# PD_USB.net
KiCad netlist of a schematic drawn in Altium Designer
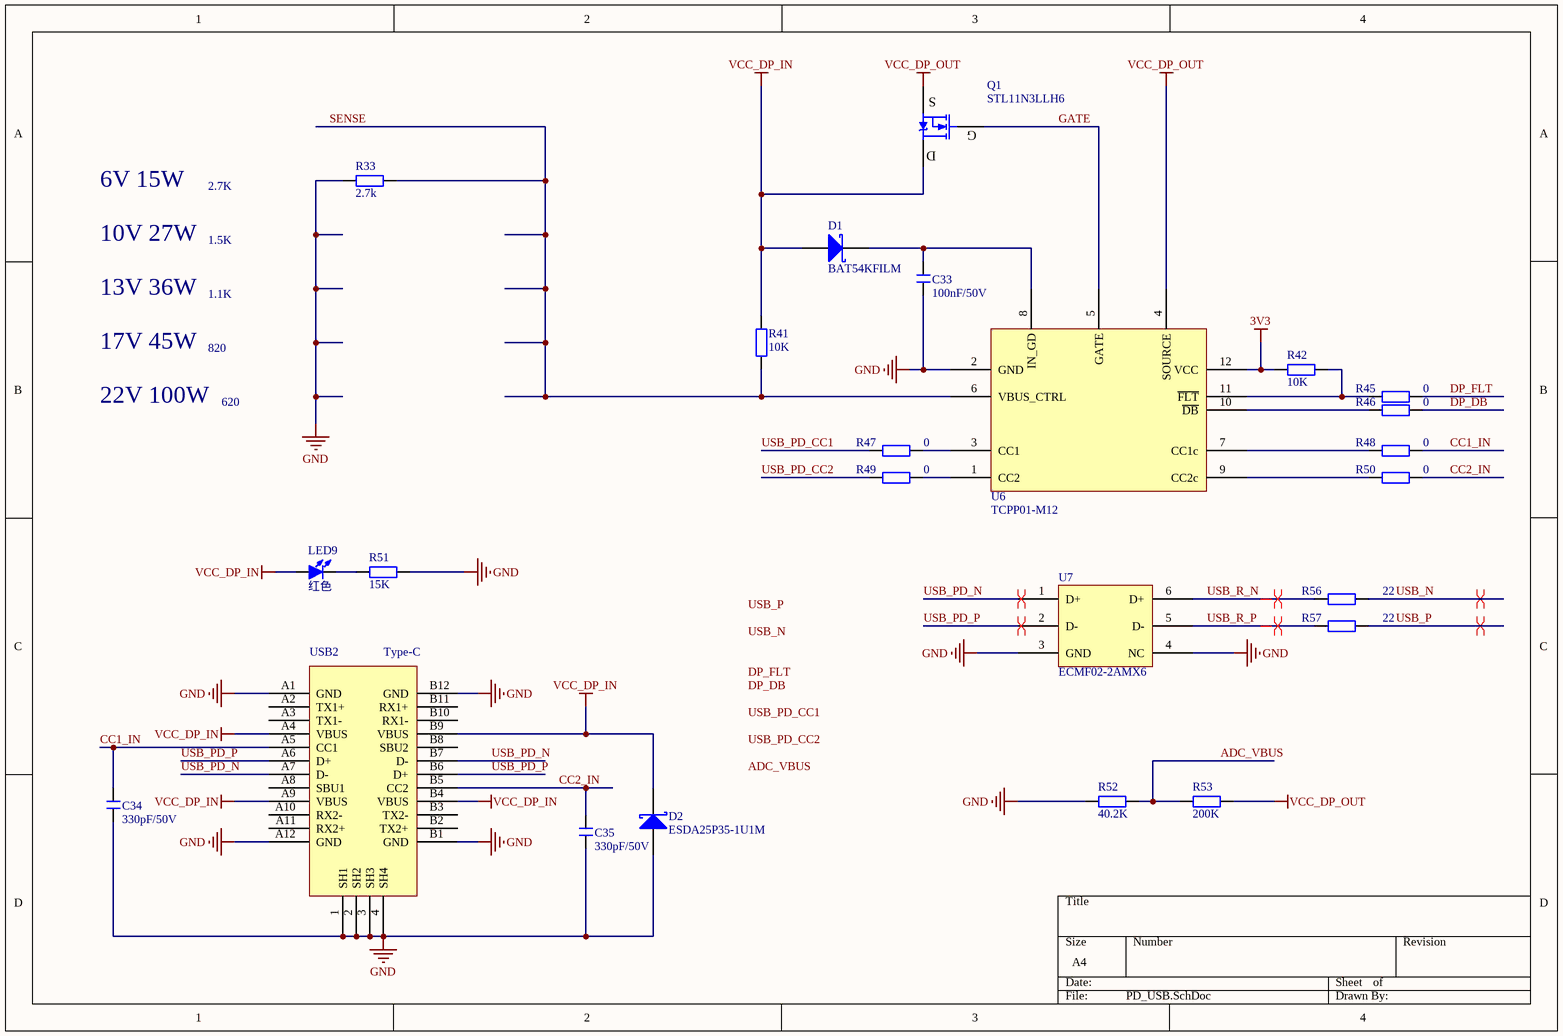
[diagram p0: PD_USB.SchDoc]

(export (version "E")
  (design (tool "Eeschema 10.0.6"))
  (components
    (comp (ref "C33")
      (value "100nF/50V")
      (footprint "C 0402_L")
      (description "贴片电容")
      (libsource (lib "3.1   - 电阻-电容-电感") (part "C"))
    )
    (comp (ref "C34")
      (value "330pF/50V")
      (footprint "C 0402_L")
      (description "贴片电容")
      (libsource (lib "3.1   - 电阻-电容-电感") (part "C"))
    )
    (comp (ref "C35")
      (value "330pF/50V")
      (footprint "C 0402_L")
      (description "贴片电容")
      (libsource (lib "3.1   - 电阻-电容-电感") (part "C"))
    )
    (comp (ref "D1")
      (value "BAT54KFILM")
      (footprint "BAT54KFILM")
      (description "Schottky Diode")
      (libsource (lib "Miscellaneous Devices") (part "D Schottky"))
    )
    (comp (ref "D2")
      (value "ESDA25P35-1U1M")
      (footprint "ESDA25P35-1U1M")
      (description "Schottky Diode")
      (libsource (lib "Miscellaneous Devices") (part "D Schottky"))
    )
    (comp (ref "LED9")
      (value "红色")
      (footprint "LED")
      (description "C84267")
      (libsource (lib "9.1   - LED") (part "LED-SMD"))
    )
    (comp (ref "Q1")
      (value "STL11N3LLH6")
      (footprint "STL11N3LLH6")
      (description "N沟道场效应管")
      (libsource (lib "6.1   - 场效应管-可控硅") (part "SI2302"))
    )
    (comp (ref "R33")
      (value "2.7k")
      (footprint "R 0402_L")
      (description "贴片电阻")
      (libsource (lib "3.1   - 电阻-电容-电感") (part "R"))
    )
    (comp (ref "R41")
      (value "10K")
      (footprint "R 0402_L")
      (description "贴片电阻")
      (libsource (lib "3.1   - 电阻-电容-电感") (part "R"))
    )
    (comp (ref "R42")
      (value "10K")
      (footprint "R 0402_L")
      (description "贴片电阻")
      (libsource (lib "3.1   - 电阻-电容-电感") (part "R"))
    )
    (comp (ref "R45")
      (value "0")
      (footprint "R 0402_L")
      (description "贴片电阻")
      (libsource (lib "3.1   - 电阻-电容-电感") (part "R"))
    )
    (comp (ref "R46")
      (value "0")
      (footprint "R 0402_L")
      (description "贴片电阻")
      (libsource (lib "3.1   - 电阻-电容-电感") (part "R"))
    )
    (comp (ref "R47")
      (value "0")
      (footprint "R 0402_L")
      (description "贴片电阻")
      (libsource (lib "3.1   - 电阻-电容-电感") (part "R"))
    )
    (comp (ref "R48")
      (value "0")
      (footprint "R 0402_L")
      (description "贴片电阻")
      (libsource (lib "3.1   - 电阻-电容-电感") (part "R"))
    )
    (comp (ref "R49")
      (value "0")
      (footprint "R 0402_L")
      (description "贴片电阻")
      (libsource (lib "3.1   - 电阻-电容-电感") (part "R"))
    )
    (comp (ref "R50")
      (value "0")
      (footprint "R 0402_L")
      (description "贴片电阻")
      (libsource (lib "3.1   - 电阻-电容-电感") (part "R"))
    )
    (comp (ref "R51")
      (value "15K")
      (footprint "R 0402_L")
      (description "贴片电阻 0402 5%")
      (libsource (lib "3.1   - 电阻-电容-电感") (part "R"))
    )
    (comp (ref "R52")
      (value "40.2K")
      (footprint "R 0402_L")
      (description "贴片电阻")
      (libsource (lib "3.1   - 电阻-电容-电感") (part "R"))
    )
    (comp (ref "R53")
      (value "200K")
      (footprint "R 0402_L")
      (description "贴片电阻")
      (libsource (lib "3.1   - 电阻-电容-电感") (part "R"))
    )
    (comp (ref "R56")
      (value "22")
      (footprint "R 0402_L")
      (description "贴片电阻")
      (libsource (lib "3.1   - 电阻-电容-电感") (part "R"))
    )
    (comp (ref "R57")
      (value "22")
      (footprint "R 0402_L")
      (description "贴片电阻")
      (libsource (lib "3.1   - 电阻-电容-电感") (part "R"))
    )
    (comp (ref "U6")
      (value "TCPP01-M12")
      (footprint "TCPP01-M12")
      (libsource (lib "2021-04-22_13-53-57") (part "TCPP01-M12"))
    )
    (comp (ref "U7")
      (value "ECMF02-2AMX6")
      (footprint "ECMF02-2AMX6")
      (libsource (lib "2021-04-22_13-53-57") (part "ECMF02-2AMX6"))
    )
    (comp (ref "USB2")
      (value "Type-C")
      (footprint "Type-c接口")
      (libsource (lib "MyPcbLib") (part "USB-Type-C-TOP"))
    )
  )
  (nets
    (net (code "1") (name "/ADC_VBUS") (class "Default")
      (node (ref "R52") (pin "1") (pinfunction "1_1") (pintype "passive"))
      (node (ref "R53") (pin "2") (pinfunction "2_2") (pintype "passive"))
    )
    (net (code "2") (name "/CC1_IN") (class "Default")
      (node (ref "C34") (pin "2") (pinfunction "2_2") (pintype "passive"))
      (node (ref "R48") (pin "2") (pinfunction "2_2") (pintype "passive"))
      (node (ref "USB2") (pin "A5") (pinfunction "CC1_A5") (pintype "passive"))
    )
    (net (code "3") (name "/CC2_IN") (class "Default")
      (node (ref "C35") (pin "2") (pinfunction "2_2") (pintype "passive"))
      (node (ref "R50") (pin "2") (pinfunction "2_2") (pintype "passive"))
      (node (ref "USB2") (pin "B5") (pinfunction "CC2_B5") (pintype "passive"))
    )
    (net (code "4") (name "/DP_DB") (class "Default")
      (node (ref "R46") (pin "2") (pinfunction "2_2") (pintype "passive"))
    )
    (net (code "5") (name "/DP_FLT") (class "Default")
      (node (ref "R45") (pin "2") (pinfunction "2_2") (pintype "passive"))
    )
    (net (code "6") (name "/GATE") (class "Default")
      (node (ref "Q1") (pin "1") (pinfunction "G_1") (pintype "passive"))
      (node (ref "U6") (pin "5") (pinfunction "GATE_5") (pintype "passive"))
    )
    (net (code "7") (name "/SENSE") (class "Default")
      (node (ref "R33") (pin "2") (pinfunction "2_2") (pintype "passive"))
      (node (ref "R41") (pin "1") (pinfunction "1_1") (pintype "passive"))
      (node (ref "U6") (pin "6") (pinfunction "VBUS_CTRL_6") (pintype "passive"))
    )
    (net (code "8") (name "/USB_N") (class "Default")
      (node (ref "R56") (pin "1") (pinfunction "1_1") (pintype "passive"))
    )
    (net (code "9") (name "/USB_P") (class "Default")
      (node (ref "R57") (pin "1") (pinfunction "1_1") (pintype "passive"))
    )
    (net (code "10") (name "/USB_PD_CC1") (class "Default")
      (node (ref "R47") (pin "1") (pinfunction "1_1") (pintype "passive"))
    )
    (net (code "11") (name "/USB_PD_CC2") (class "Default")
      (node (ref "R49") (pin "1") (pinfunction "1_1") (pintype "passive"))
    )
    (net (code "12") (name "/USB_PD_N") (class "Default")
      (node (ref "U7") (pin "1") (pinfunction "D+_1") (pintype "passive"))
      (node (ref "USB2") (pin "A7") (pinfunction "D-_A7") (pintype "passive"))
      (node (ref "USB2") (pin "B7") (pinfunction "D-_B7") (pintype "passive"))
    )
    (net (code "13") (name "/USB_PD_P") (class "Default")
      (node (ref "U7") (pin "2") (pinfunction "D-_2") (pintype "passive"))
      (node (ref "USB2") (pin "A6") (pinfunction "D+_A6") (pintype "passive"))
      (node (ref "USB2") (pin "B6") (pinfunction "D+_B6") (pintype "passive"))
    )
    (net (code "14") (name "/USB_R_N") (class "Default")
      (node (ref "R56") (pin "2") (pinfunction "2_2") (pintype "passive"))
      (node (ref "U7") (pin "6") (pinfunction "D+_6") (pintype "passive"))
    )
    (net (code "15") (name "/USB_R_P") (class "Default")
      (node (ref "R57") (pin "2") (pinfunction "2_2") (pintype "passive"))
      (node (ref "U7") (pin "5") (pinfunction "D-_5") (pintype "passive"))
    )
    (net (code "16") (name "3V3") (class "Default")
      (node (ref "R42") (pin "2") (pinfunction "2_2") (pintype "passive"))
      (node (ref "U6") (pin "12") (pinfunction "VCC_12") (pintype "passive"))
    )
    (net (code "17") (name "GND") (class "Default")
      (node (ref "C33") (pin "1") (pinfunction "1_1") (pintype "passive"))
      (node (ref "C34") (pin "1") (pinfunction "1_1") (pintype "passive"))
      (node (ref "C35") (pin "1") (pinfunction "1_1") (pintype "passive"))
      (node (ref "D2") (pin "1") (pinfunction "A_1") (pintype "passive"))
      (node (ref "R33") (pin "1") (pinfunction "1_1") (pintype "passive"))
      (node (ref "R51") (pin "1") (pinfunction "1_1") (pintype "passive"))
      (node (ref "R52") (pin "2") (pinfunction "2_2") (pintype "passive"))
      (node (ref "U6") (pin "2") (pinfunction "GND_2") (pintype "passive"))
      (node (ref "U7") (pin "3") (pinfunction "GND_3") (pintype "passive"))
      (node (ref "U7") (pin "4") (pinfunction "NC_4") (pintype "passive"))
      (node (ref "USB2") (pin "1") (pinfunction "SH1_1") (pintype "passive"))
      (node (ref "USB2") (pin "2") (pinfunction "SH2_2") (pintype "passive"))
      (node (ref "USB2") (pin "3") (pinfunction "SH3_3") (pintype "passive"))
      (node (ref "USB2") (pin "4") (pinfunction "SH4_4") (pintype "passive"))
      (node (ref "USB2") (pin "A1") (pinfunction "GND_A1") (pintype "passive"))
      (node (ref "USB2") (pin "A12") (pinfunction "GND_A12") (pintype "passive"))
      (node (ref "USB2") (pin "B1") (pinfunction "GND_B1") (pintype "passive"))
      (node (ref "USB2") (pin "B12") (pinfunction "GND_B12") (pintype "passive"))
    )
    (net (code "18") (name "Net-(D1-K)") (class "Default")
      (node (ref "C33") (pin "2") (pinfunction "2_2") (pintype "passive"))
      (node (ref "D1") (pin "2") (pinfunction "K_2") (pintype "passive"))
      (node (ref "U6") (pin "8") (pinfunction "IN_GD_8") (pintype "passive"))
    )
    (net (code "19") (name "Net-(LED9-K)") (class "Default")
      (node (ref "LED9") (pin "2") (pinfunction "K_2") (pintype "passive"))
      (node (ref "R51") (pin "2") (pinfunction "2_2") (pintype "passive"))
    )
    (net (code "20") (name "Net-(U6-CC1)") (class "Default")
      (node (ref "R47") (pin "2") (pinfunction "2_2") (pintype "passive"))
      (node (ref "U6") (pin "3") (pinfunction "CC1_3") (pintype "passive"))
    )
    (net (code "21") (name "Net-(U6-CC1c)") (class "Default")
      (node (ref "R48") (pin "1") (pinfunction "1_1") (pintype "passive"))
      (node (ref "U6") (pin "7") (pinfunction "CC1c_7") (pintype "passive"))
    )
    (net (code "22") (name "Net-(U6-CC2)") (class "Default")
      (node (ref "R49") (pin "2") (pinfunction "2_2") (pintype "passive"))
      (node (ref "U6") (pin "1") (pinfunction "CC2_1") (pintype "passive"))
    )
    (net (code "23") (name "Net-(U6-CC2c)") (class "Default")
      (node (ref "R50") (pin "1") (pinfunction "1_1") (pintype "passive"))
      (node (ref "U6") (pin "9") (pinfunction "CC2c_9") (pintype "passive"))
    )
    (net (code "24") (name "Net-(U6-~{DB})") (class "Default")
      (node (ref "R46") (pin "1") (pinfunction "1_1") (pintype "passive"))
      (node (ref "U6") (pin "10") (pinfunction "~{DB}_10") (pintype "passive"))
    )
    (net (code "25") (name "Net-(U6-~{FLT})") (class "Default")
      (node (ref "R42") (pin "1") (pinfunction "1_1") (pintype "passive"))
      (node (ref "R45") (pin "1") (pinfunction "1_1") (pintype "passive"))
      (node (ref "U6") (pin "11") (pinfunction "~{FLT}_11") (pintype "passive"))
    )
    (net (code "26") (name "VCC_DP_IN") (class "Default")
      (node (ref "D1") (pin "1") (pinfunction "A_1") (pintype "passive"))
      (node (ref "D2") (pin "2") (pinfunction "K_2") (pintype "passive"))
      (node (ref "LED9") (pin "1") (pinfunction "A_1") (pintype "passive"))
      (node (ref "Q1") (pin "3") (pinfunction "D_3") (pintype "passive"))
      (node (ref "R41") (pin "2") (pinfunction "2_2") (pintype "passive"))
      (node (ref "USB2") (pin "A4") (pinfunction "VBUS_A4") (pintype "passive"))
      (node (ref "USB2") (pin "A9") (pinfunction "VBUS_A9") (pintype "passive"))
      (node (ref "USB2") (pin "B4") (pinfunction "VBUS_B4") (pintype "passive"))
      (node (ref "USB2") (pin "B9") (pinfunction "VBUS_B9") (pintype "passive"))
    )
    (net (code "27") (name "VCC_DP_OUT") (class "Default")
      (node (ref "Q1") (pin "2") (pinfunction "S_2") (pintype "passive"))
      (node (ref "R53") (pin "1") (pinfunction "1_1") (pintype "passive"))
      (node (ref "U6") (pin "4") (pinfunction "SOURCE_4") (pintype "passive"))
    )
    (net (code "28") (name "unconnected-(USB2-RX1+-PadB11)") (class "Default")
      (node (ref "USB2") (pin "B11") (pinfunction "RX1+_B11") (pintype "passive"))
    )
    (net (code "29") (name "unconnected-(USB2-RX1--PadB10)") (class "Default")
      (node (ref "USB2") (pin "B10") (pinfunction "RX1-_B10") (pintype "passive"))
    )
    (net (code "30") (name "unconnected-(USB2-RX2+-PadA11)") (class "Default")
      (node (ref "USB2") (pin "A11") (pinfunction "RX2+_A11") (pintype "passive"))
    )
    (net (code "31") (name "unconnected-(USB2-RX2--PadA10)") (class "Default")
      (node (ref "USB2") (pin "A10") (pinfunction "RX2-_A10") (pintype "passive"))
    )
    (net (code "32") (name "unconnected-(USB2-SBU1-PadA8)") (class "Default")
      (node (ref "USB2") (pin "A8") (pinfunction "SBU1_A8") (pintype "passive"))
    )
    (net (code "33") (name "unconnected-(USB2-SBU2-PadB8)") (class "Default")
      (node (ref "USB2") (pin "B8") (pinfunction "SBU2_B8") (pintype "passive"))
    )
    (net (code "34") (name "unconnected-(USB2-TX1+-PadA2)") (class "Default")
      (node (ref "USB2") (pin "A2") (pinfunction "TX1+_A2") (pintype "passive"))
    )
    (net (code "35") (name "unconnected-(USB2-TX1--PadA3)") (class "Default")
      (node (ref "USB2") (pin "A3") (pinfunction "TX1-_A3") (pintype "passive"))
    )
    (net (code "36") (name "unconnected-(USB2-TX2+-PadB2)") (class "Default")
      (node (ref "USB2") (pin "B2") (pinfunction "TX2+_B2") (pintype "passive"))
    )
    (net (code "37") (name "unconnected-(USB2-TX2--PadB3)") (class "Default")
      (node (ref "USB2") (pin "B3") (pinfunction "TX2-_B3") (pintype "passive"))
    )
  )
)
